# 4_27.net
KiCad netlist of a schematic drawn in EasyEDA
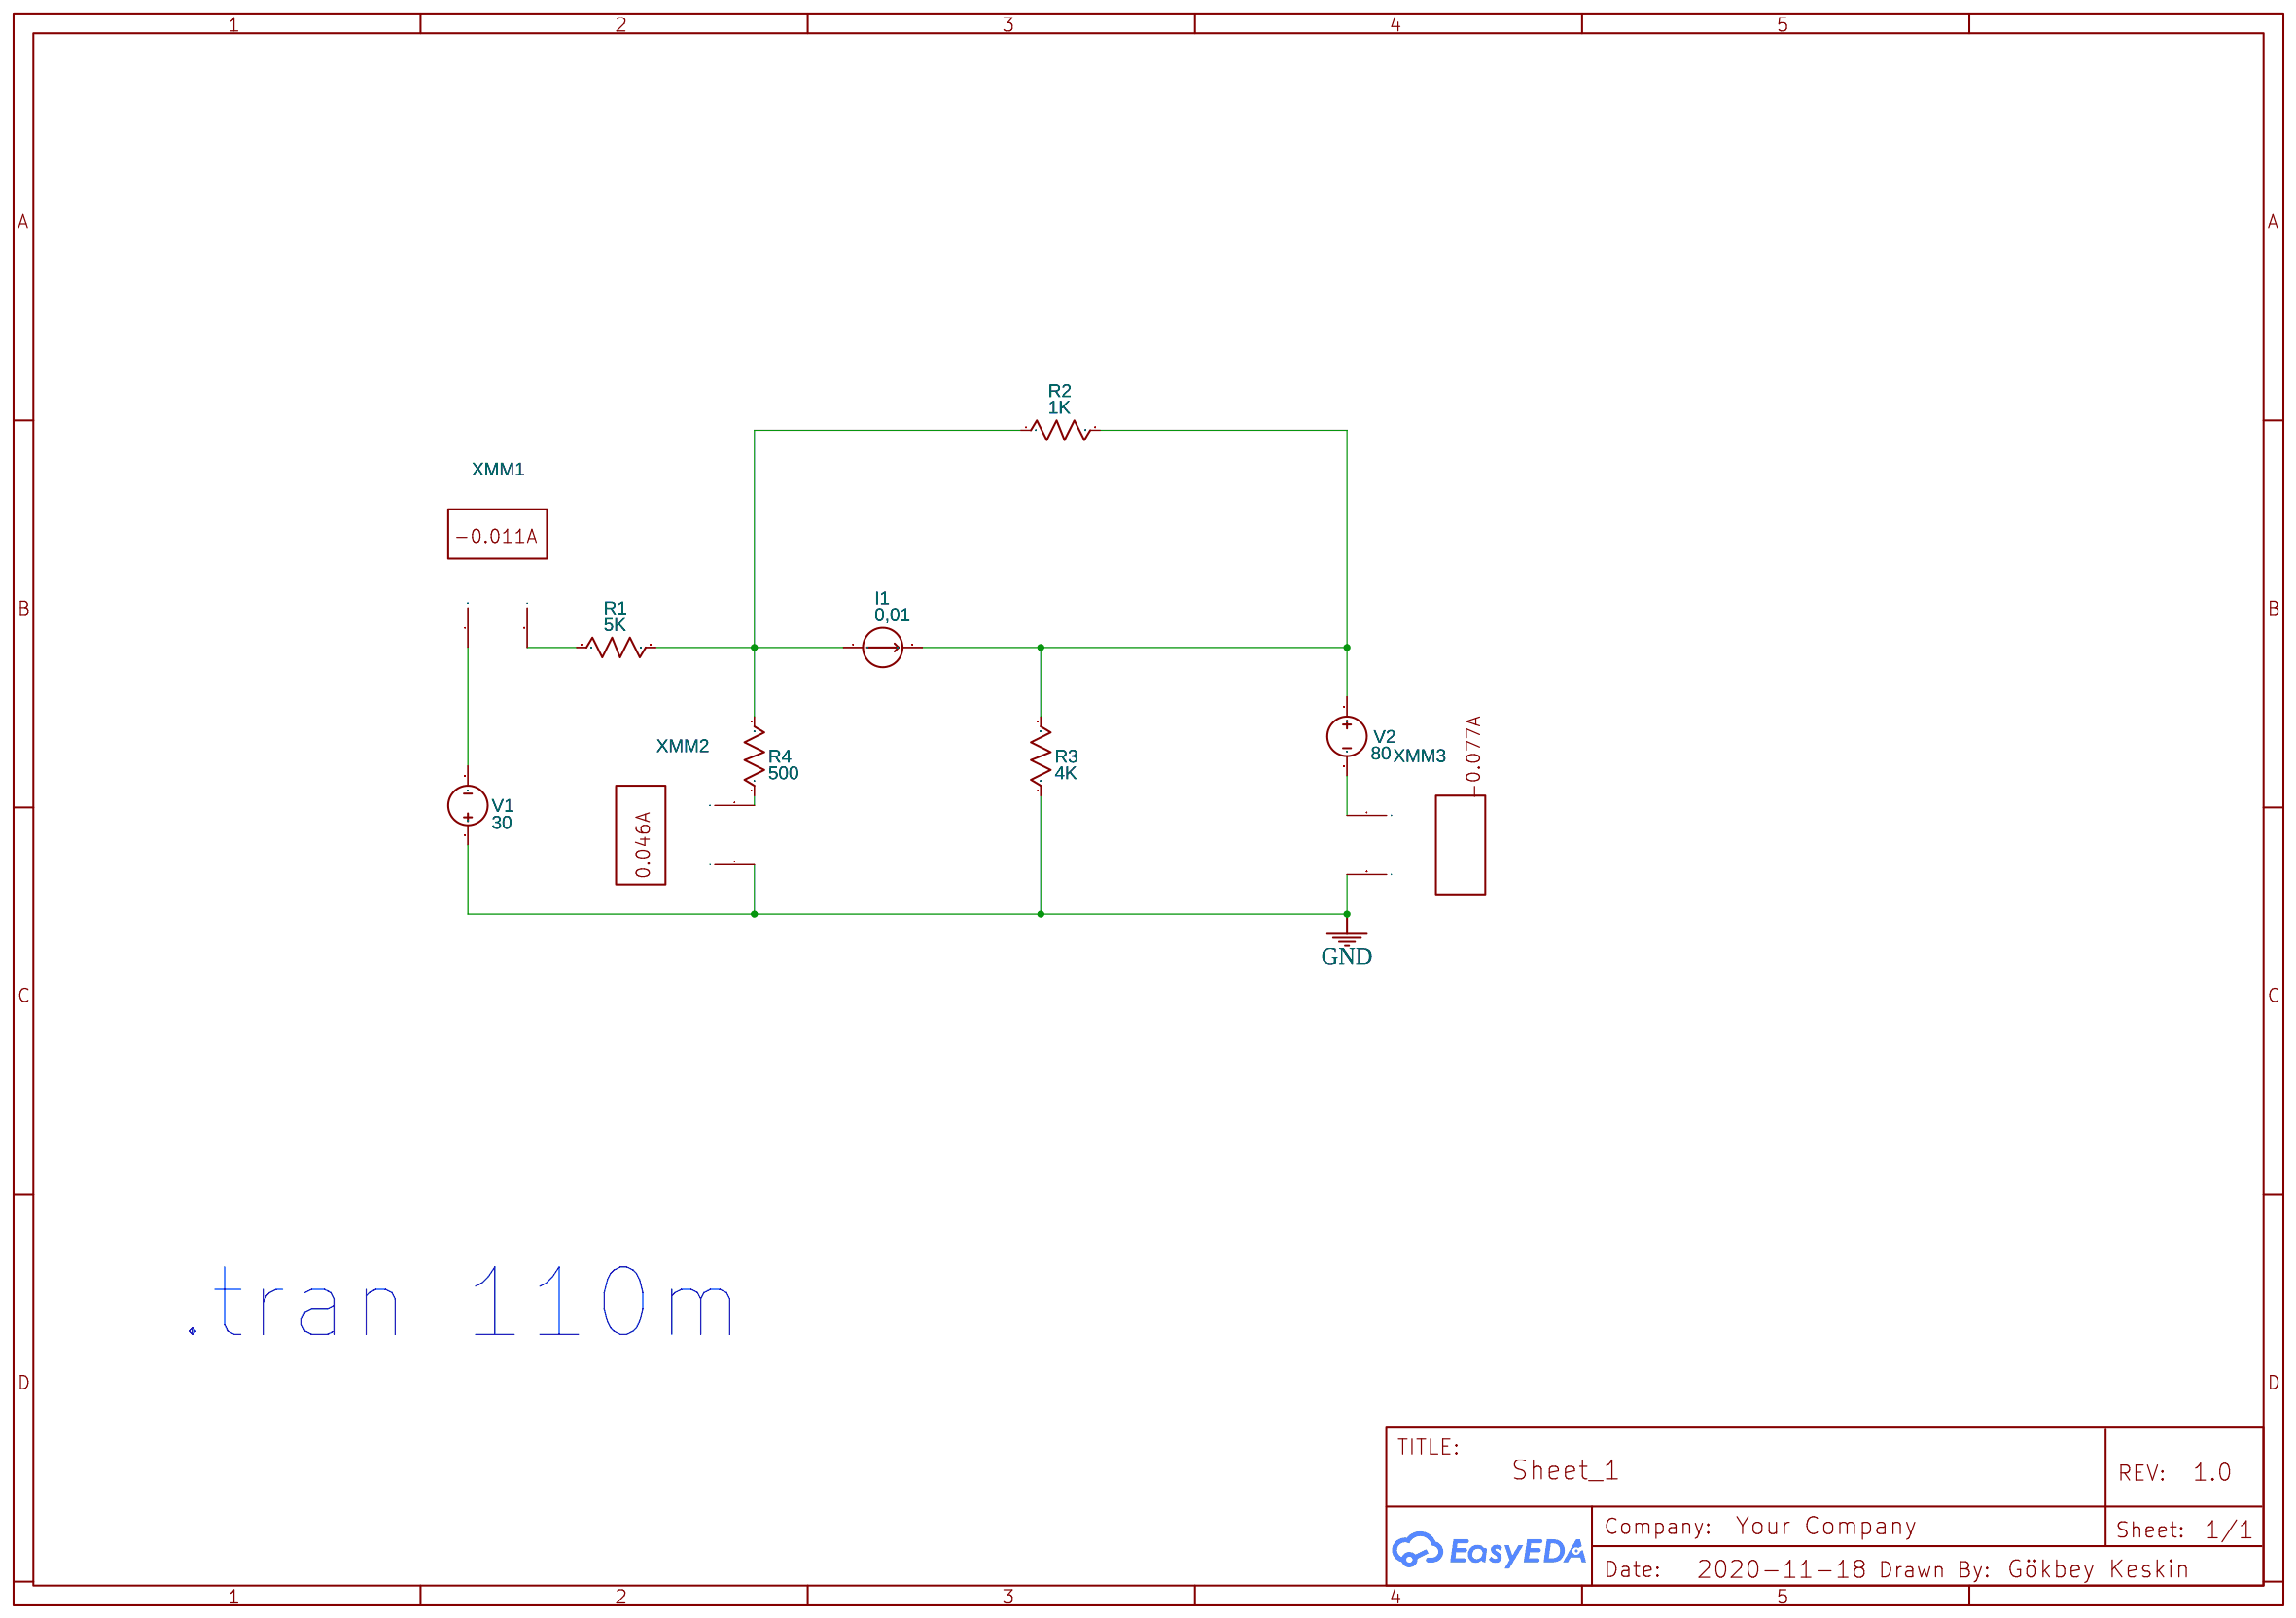
[diagram p0: schematic sheet]

(export (version "E")
  (design (tool "Eeschema 10.0.6"))
  (components
    (comp (ref "I1") (value "0,01") (libsource (lib "") (part "IDC")))
    (comp (ref "R1") (value "5K") (libsource (lib "") (part "Resistor_US_1")))
    (comp (ref "R2") (value "1K") (libsource (lib "") (part "Resistor_US_1")))
    (comp (ref "R3") (value "4K") (libsource (lib "") (part "Resistor_US")))
    (comp (ref "R4") (value "500") (libsource (lib "") (part "Resistor_US")))
    (comp (ref "V1") (value "30") (libsource (lib "") (part "VDC")))
    (comp (ref "V2") (value "80") (libsource (lib "") (part "VDC_1")))
    (comp (ref "XMM1") (value "Multimeter") (libsource (lib "") (part "MULTIMETER_2")))
    (comp (ref "XMM2") (value "Multimeter") (libsource (lib "") (part "MULTIMETER")))
    (comp (ref "XMM3") (value "Multimeter") (libsource (lib "") (part "MULTIMETER_1")))
  )
  (nets
    (net (code "1") (name "GND") (class "Default")
      (node (ref "R3") (pin "1") (pinfunction "1_1") (pintype "unspecified"))
      (node (ref "V1") (pin "1") (pinfunction "1_1") (pintype "unspecified"))
      (node (ref "XMM2") (pin "2") (pinfunction "I_2") (pintype "unspecified"))
      (node (ref "XMM3") (pin "2") (pinfunction "I_2") (pintype "unspecified"))
    )
    (net (code "2") (name "Net-(I1-Pad1)") (class "Default")
      (node (ref "I1") (pin "1") (pinfunction "1_1") (pintype "unspecified"))
      (node (ref "R1") (pin "2") (pinfunction "2_2") (pintype "unspecified"))
      (node (ref "R2") (pin "1") (pinfunction "1_1") (pintype "unspecified"))
      (node (ref "R4") (pin "2") (pinfunction "2_2") (pintype "unspecified"))
    )
    (net (code "3") (name "Net-(I1-Pad2)") (class "Default")
      (node (ref "I1") (pin "2") (pinfunction "2_2") (pintype "unspecified"))
      (node (ref "R2") (pin "2") (pinfunction "2_2") (pintype "unspecified"))
      (node (ref "R3") (pin "2") (pinfunction "2_2") (pintype "unspecified"))
      (node (ref "V2") (pin "1") (pinfunction "1_1") (pintype "unspecified"))
    )
    (net (code "4") (name "Net-(XMM1-+)") (class "Default")
      (node (ref "V1") (pin "2") (pinfunction "2_2") (pintype "unspecified"))
      (node (ref "XMM1") (pin "1") (pinfunction "+_1") (pintype "unspecified"))
    )
    (net (code "5") (name "Net-(XMM1-I)") (class "Default")
      (node (ref "R1") (pin "1") (pinfunction "1_1") (pintype "unspecified"))
      (node (ref "XMM1") (pin "2") (pinfunction "I_2") (pintype "unspecified"))
    )
    (net (code "6") (name "Net-(XMM2-+)") (class "Default")
      (node (ref "R4") (pin "1") (pinfunction "1_1") (pintype "unspecified"))
      (node (ref "XMM2") (pin "1") (pinfunction "+_1") (pintype "unspecified"))
    )
    (net (code "7") (name "Net-(XMM3-+)") (class "Default")
      (node (ref "V2") (pin "2") (pinfunction "2_2") (pintype "unspecified"))
      (node (ref "XMM3") (pin "1") (pinfunction "+_1") (pintype "unspecified"))
    )
  )
)
